# Enkoder.net
KiCad netlist of a schematic drawn in Altium Designer
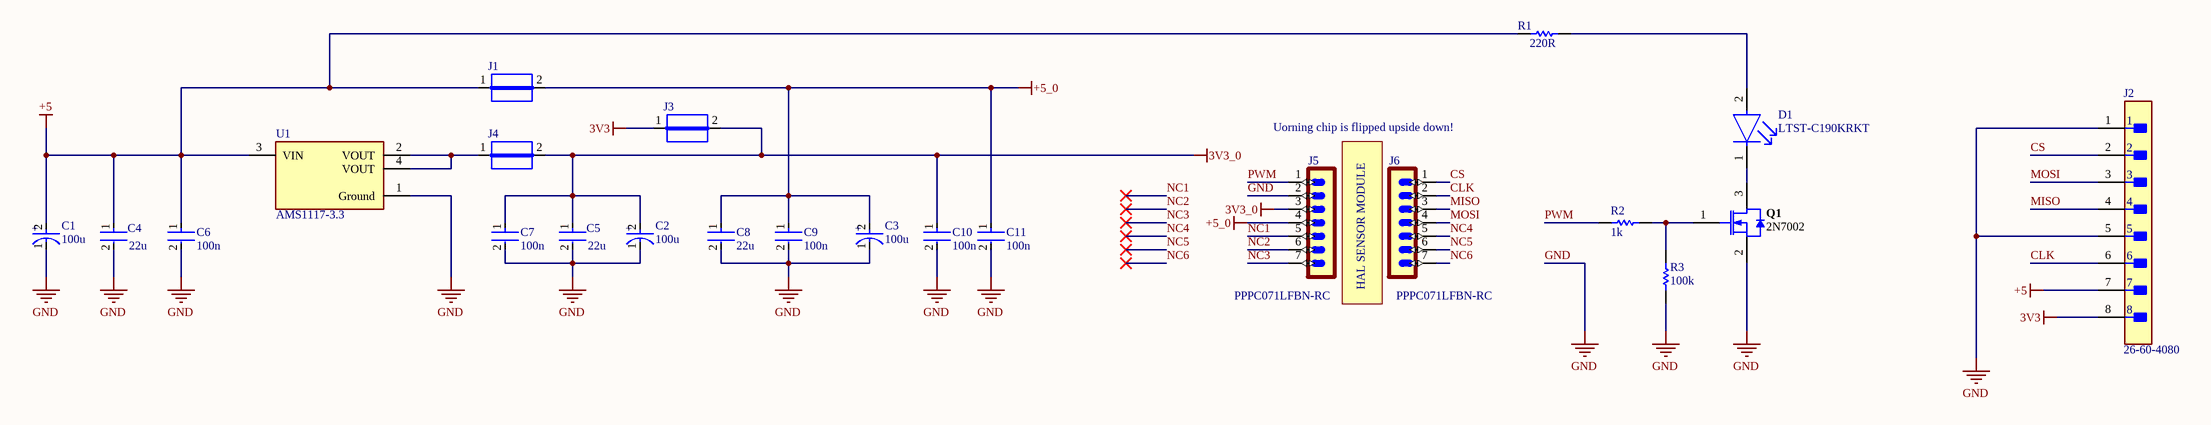
[diagram p0: Enkoder.SchDoc]

(export (version "E")
  (design (tool "Eeschema 10.0.6"))
  (components
    (comp (ref "C1")
      (value "100u")
      (footprint "FP-FTF-MFG")
      (description "CAP ALUM 220UF 20% 50V SMD")
      (fields (field (name "TOLERANCE") "20%") (field (name "VOLTAGE") "50V"))
      (libsource (lib "Altium Content Vault") (part "203bc49f2ac43e59fd269a8c329ed05"))
    )
    (comp (ref "C2")
      (value "100u")
      (footprint "FP-FTF-MFG")
      (description "CAP ALUM 220UF 20% 50V SMD")
      (fields (field (name "TOLERANCE") "20%") (field (name "VOLTAGE") "50V"))
      (libsource (lib "Altium Content Vault") (part "203bc49f2ac43e59fd269a8c329ed05"))
    )
    (comp (ref "C3")
      (value "100u")
      (footprint "FP-FTF-MFG")
      (description "CAP ALUM 220UF 20% 50V SMD")
      (fields (field (name "TOLERANCE") "20%") (field (name "VOLTAGE") "50V"))
      (libsource (lib "Altium Content Vault") (part "203bc49f2ac43e59fd269a8c329ed05"))
    )
    (comp (ref "C4")
      (value "22u")
      (footprint "FP-C3216-085-0_2-MFG")
      (description "Multilayer Ceramic Capacitors 22μF ±20% 6.3V X5R SMD 1206")
      (fields (field (name "TOLERANCE") "20%"))
      (libsource (lib "Altium Content Vault") (part "11868f565c42a9108669ba33697ecf6"))
    )
    (comp (ref "C5")
      (value "22u")
      (footprint "FP-C3216-085-0_2-MFG")
      (description "Multilayer Ceramic Capacitors 22μF ±20% 6.3V X5R SMD 1206")
      (fields (field (name "TOLERANCE") "20%"))
      (libsource (lib "Altium Content Vault") (part "11868f565c42a9108669ba33697ecf6"))
    )
    (comp (ref "C6")
      (value "100n")
      (footprint "FP-C0603C-CF-MFG")
      (description "CAP CER 0.1UF 50V X7R 0603")
      (fields (field (name "TOLERANCE") "0.1") (field (name "MANUFACTURER") "KEMET"))
      (libsource (lib "Altium Content Vault") (part "b4654b650e69147ec39a6b967a45e02"))
    )
    (comp (ref "C7")
      (value "100n")
      (footprint "FP-C0603C-CF-MFG")
      (description "CAP CER 0.1UF 50V X7R 0603")
      (fields (field (name "TOLERANCE") "0.1") (field (name "MANUFACTURER") "KEMET"))
      (libsource (lib "Altium Content Vault") (part "b4654b650e69147ec39a6b967a45e02"))
    )
    (comp (ref "C8")
      (value "22u")
      (footprint "FP-C3216-085-0_2-MFG")
      (description "Multilayer Ceramic Capacitors 22μF ±20% 6.3V X5R SMD 1206")
      (fields (field (name "TOLERANCE") "20%"))
      (libsource (lib "Altium Content Vault") (part "11868f565c42a9108669ba33697ecf6"))
    )
    (comp (ref "C9")
      (value "100n")
      (footprint "FP-C0603C-CF-MFG")
      (description "CAP CER 0.1UF 50V X7R 0603")
      (fields (field (name "TOLERANCE") "0.1") (field (name "MANUFACTURER") "KEMET"))
      (libsource (lib "Altium Content Vault") (part "b4654b650e69147ec39a6b967a45e02"))
    )
    (comp (ref "C10")
      (value "100n")
      (footprint "FP-C0603C-CF-MFG")
      (description "CAP CER 0.1UF 50V X7R 0603")
      (fields (field (name "TOLERANCE") "0.1") (field (name "MANUFACTURER") "KEMET"))
      (libsource (lib "Altium Content Vault") (part "b4654b650e69147ec39a6b967a45e02"))
    )
    (comp (ref "C11")
      (value "100n")
      (footprint "FP-C0603C-CF-MFG")
      (description "CAP CER 0.1UF 50V X7R 0603")
      (fields (field (name "TOLERANCE") "0.1") (field (name "MANUFACTURER") "KEMET"))
      (libsource (lib "Altium Content Vault") (part "b4654b650e69147ec39a6b967a45e02"))
    )
    (comp (ref "D1")
      (value "LTST-C190KRKT")
      (footprint "FP-LTST-C190KRKT-MFG")
      (description "LED RED CLEAR CHIP SMD")
      (libsource (lib "Altium Content Vault") (part "8706943c75ba83719d021d2fdc84c58"))
    )
    (comp (ref "J1") (value "JUMPER") (footprint "JUMPER") (libsource (lib "WUST") (part "JUMPER")))
    (comp (ref "J2")
      (value "26-60-4080")
      (footprint "FP-26-60-4080-MFG")
      (libsource (lib "Altium Content Vault") (part "99ec2b232beb5d2356d4d77f6a047f0"))
    )
    (comp (ref "J3") (value "JUMPER") (footprint "JUMPER") (libsource (lib "WUST") (part "JUMPER")))
    (comp (ref "J4") (value "JUMPER") (footprint "JUMPER") (libsource (lib "WUST") (part "JUMPER")))
    (comp (ref "J5")
      (value "PPPC071LFBN-RC")
      (footprint "1X07-PIN")
      (description "7 Position Header Connector 0.100 (2.54mm) Through Hole Gold")
      (fields (field (name "MF") "Sullins Connector"))
      (libsource (lib "") (part "PPPC071LFBN-RC_1"))
    )
    (comp (ref "J6")
      (value "PPPC071LFBN-RC")
      (footprint "1X07-PIN")
      (description "7 Position Header Connector 0.100 (2.54mm) Through Hole Gold")
      (fields (field (name "MF") "Sullins Connector"))
      (libsource (lib "WUST") (part "PPPC071LFBN-RC"))
    )
    (comp (ref "Q1")
      (value "2N7002")
      (footprint "INF-PG-SOT23_M")
      (fields (field (name "MANUFACTURER") "Infineon"))
      (libsource (lib "Altium Content Vault") (part "INF-NDMOS-GSD-3"))
    )
    (comp (ref "R1")
      (value "220R")
      (footprint "RESC0603(1608)_N")
      (description "0.1W 1% 0603 (1608 Metric)  SMD")
      (fields (field (name "TOLERANCE") "5 %") (field (name "POWER") "0.1 W"))
      (libsource (lib "Altium Content Vault") (part "RES"))
    )
    (comp (ref "R2")
      (value "1k")
      (footprint "RESC0603(1608)_N")
      (description "2K 0.1W 5% 0603 (1608 Metric)  SMD")
      (fields (field (name "TOLERANCE") "5 %") (field (name "POWER") "0.1 W"))
      (libsource (lib "Altium Content Vault") (part "RES"))
    )
    (comp (ref "R3")
      (value "100k")
      (footprint "RESC0603(1608)_N")
      (description "2K 0.1W 5% 0603 (1608 Metric)  SMD")
      (fields (field (name "TOLERANCE") "5 %") (field (name "POWER") "0.1 W"))
      (libsource (lib "Altium Content Vault") (part "RES"))
    )
    (comp (ref "U1")
      (value "AMS1117-3.3")
      (footprint "FP-AMS1117-IPC_C")
      (description "LDO Voltage Regulators 1A, 3.3V")
      (fields
        (field (name "OCTOPART") "https://octopart.com/ams1117-3.3-advanced+monolithic+systems-25899300")
        (field (name "MANUFACTURER") "Advanced Monolithic Systems")
      )
      (libsource (lib "Altium Content Vault") (part "8bdbb5f8e77002000e30dd2845d0354"))
    )
  )
  (nets
    (net (code "1") (name "+5") (class "Default")
      (node (ref "C1") (pin "2") (pinfunction "A_2") (pintype "passive"))
      (node (ref "C4") (pin "1") (pinfunction "1_1") (pintype "passive"))
      (node (ref "C6") (pin "1") (pinfunction "1_1") (pintype "passive"))
      (node (ref "J1") (pin "1") (pinfunction "1_1") (pintype "passive"))
      (node (ref "J2") (pin "7") (pinfunction "7_7") (pintype "passive"))
      (node (ref "R1") (pin "2") (pinfunction "2_2") (pintype "passive"))
      (node (ref "U1") (pin "3") (pinfunction "VIN_3") (pintype "power_in"))
    )
    (net (code "2") (name "+5_0") (class "Default")
      (node (ref "C11") (pin "1") (pinfunction "1_1") (pintype "passive"))
      (node (ref "C3") (pin "2") (pinfunction "A_2") (pintype "passive"))
      (node (ref "C8") (pin "1") (pinfunction "1_1") (pintype "passive"))
      (node (ref "C9") (pin "1") (pinfunction "1_1") (pintype "passive"))
      (node (ref "J1") (pin "2") (pinfunction "2_2") (pintype "passive"))
      (node (ref "J5") (pin "4") (pinfunction "P$4_4") (pintype "bidirectional"))
    )
    (net (code "3") (name "/CLK") (class "Default")
      (node (ref "J2") (pin "6") (pinfunction "6_6") (pintype "passive"))
      (node (ref "J6") (pin "2") (pinfunction "P$2_2") (pintype "bidirectional"))
    )
    (net (code "4") (name "/CS") (class "Default")
      (node (ref "J2") (pin "2") (pinfunction "2_2") (pintype "passive"))
      (node (ref "J6") (pin "1") (pinfunction "P$1_1") (pintype "bidirectional"))
    )
    (net (code "5") (name "/MISO") (class "Default")
      (node (ref "J2") (pin "4") (pinfunction "4_4") (pintype "passive"))
      (node (ref "J6") (pin "3") (pinfunction "P$3_3") (pintype "bidirectional"))
    )
    (net (code "6") (name "/MOSI") (class "Default")
      (node (ref "J2") (pin "3") (pinfunction "3_3") (pintype "passive"))
      (node (ref "J6") (pin "4") (pinfunction "P$4_4") (pintype "bidirectional"))
    )
    (net (code "7") (name "/NC1") (class "Default")
      (node (ref "J5") (pin "5") (pinfunction "P$5_5") (pintype "bidirectional"))
    )
    (net (code "8") (name "/NC2") (class "Default")
      (node (ref "J5") (pin "6") (pinfunction "P$6_6") (pintype "bidirectional"))
    )
    (net (code "9") (name "/NC3") (class "Default")
      (node (ref "J5") (pin "7") (pinfunction "P$7_7") (pintype "bidirectional"))
    )
    (net (code "10") (name "/NC4") (class "Default")
      (node (ref "J6") (pin "5") (pinfunction "P$5_5") (pintype "bidirectional"))
    )
    (net (code "11") (name "/NC5") (class "Default")
      (node (ref "J6") (pin "6") (pinfunction "P$6_6") (pintype "bidirectional"))
    )
    (net (code "12") (name "/NC6") (class "Default")
      (node (ref "J6") (pin "7") (pinfunction "P$7_7") (pintype "bidirectional"))
    )
    (net (code "13") (name "/PWM") (class "Default")
      (node (ref "J5") (pin "1") (pinfunction "P$1_1") (pintype "bidirectional"))
      (node (ref "R2") (pin "2") (pinfunction "2_2") (pintype "passive"))
    )
    (net (code "14") (name "3V3") (class "Default")
      (node (ref "J2") (pin "8") (pinfunction "8_8") (pintype "passive"))
      (node (ref "J3") (pin "1") (pinfunction "1_1") (pintype "passive"))
    )
    (net (code "15") (name "3V3_0") (class "Default")
      (node (ref "C10") (pin "1") (pinfunction "1_1") (pintype "passive"))
      (node (ref "C2") (pin "2") (pinfunction "A_2") (pintype "passive"))
      (node (ref "C5") (pin "1") (pinfunction "1_1") (pintype "passive"))
      (node (ref "C7") (pin "1") (pinfunction "1_1") (pintype "passive"))
      (node (ref "J3") (pin "2") (pinfunction "2_2") (pintype "passive"))
      (node (ref "J4") (pin "2") (pinfunction "2_2") (pintype "passive"))
      (node (ref "J5") (pin "3") (pinfunction "P$3_3") (pintype "bidirectional"))
    )
    (net (code "16") (name "GND") (class "Default")
      (node (ref "C1") (pin "1") (pinfunction "C_1") (pintype "passive"))
      (node (ref "C10") (pin "2") (pinfunction "2_2") (pintype "passive"))
      (node (ref "C11") (pin "2") (pinfunction "2_2") (pintype "passive"))
      (node (ref "C2") (pin "1") (pinfunction "C_1") (pintype "passive"))
      (node (ref "C3") (pin "1") (pinfunction "C_1") (pintype "passive"))
      (node (ref "C4") (pin "2") (pinfunction "2_2") (pintype "passive"))
      (node (ref "C5") (pin "2") (pinfunction "2_2") (pintype "passive"))
      (node (ref "C6") (pin "2") (pinfunction "2_2") (pintype "passive"))
      (node (ref "C7") (pin "2") (pinfunction "2_2") (pintype "passive"))
      (node (ref "C8") (pin "2") (pinfunction "2_2") (pintype "passive"))
      (node (ref "C9") (pin "2") (pinfunction "2_2") (pintype "passive"))
      (node (ref "J2") (pin "1") (pinfunction "1_1") (pintype "passive"))
      (node (ref "J2") (pin "5") (pinfunction "5_5") (pintype "passive"))
      (node (ref "J5") (pin "2") (pinfunction "P$2_2") (pintype "bidirectional"))
      (node (ref "Q1") (pin "2") (pinfunction "SOURCE_2") (pintype "passive"))
      (node (ref "R3") (pin "2") (pinfunction "2_2") (pintype "passive"))
      (node (ref "U1") (pin "1") (pinfunction "Ground_1") (pintype "power_in"))
    )
    (net (code "17") (name "Net-(D1-A)") (class "Default")
      (node (ref "D1") (pin "2") (pinfunction "A_2") (pintype "passive"))
      (node (ref "R1") (pin "1") (pinfunction "1_1") (pintype "passive"))
    )
    (net (code "18") (name "Net-(D1-C)") (class "Default")
      (node (ref "D1") (pin "1") (pinfunction "C_1") (pintype "passive"))
      (node (ref "Q1") (pin "3") (pinfunction "DRAIN_3") (pintype "passive"))
    )
    (net (code "19") (name "Net-(J4-Pad1)") (class "Default")
      (node (ref "J4") (pin "1") (pinfunction "1_1") (pintype "passive"))
      (node (ref "U1") (pin "2") (pinfunction "VOUT_2") (pintype "passive"))
      (node (ref "U1") (pin "4") (pinfunction "VOUT_4") (pintype "passive"))
    )
    (net (code "20") (name "Net-(Q1-GATE)") (class "Default")
      (node (ref "Q1") (pin "1") (pinfunction "GATE_1") (pintype "passive"))
      (node (ref "R2") (pin "1") (pinfunction "1_1") (pintype "passive"))
      (node (ref "R3") (pin "1") (pinfunction "1_1") (pintype "passive"))
    )
  )
)
